# XMOS_TSBOARD_Xmos.net
KiCad netlist of a schematic drawn in Altium Designer
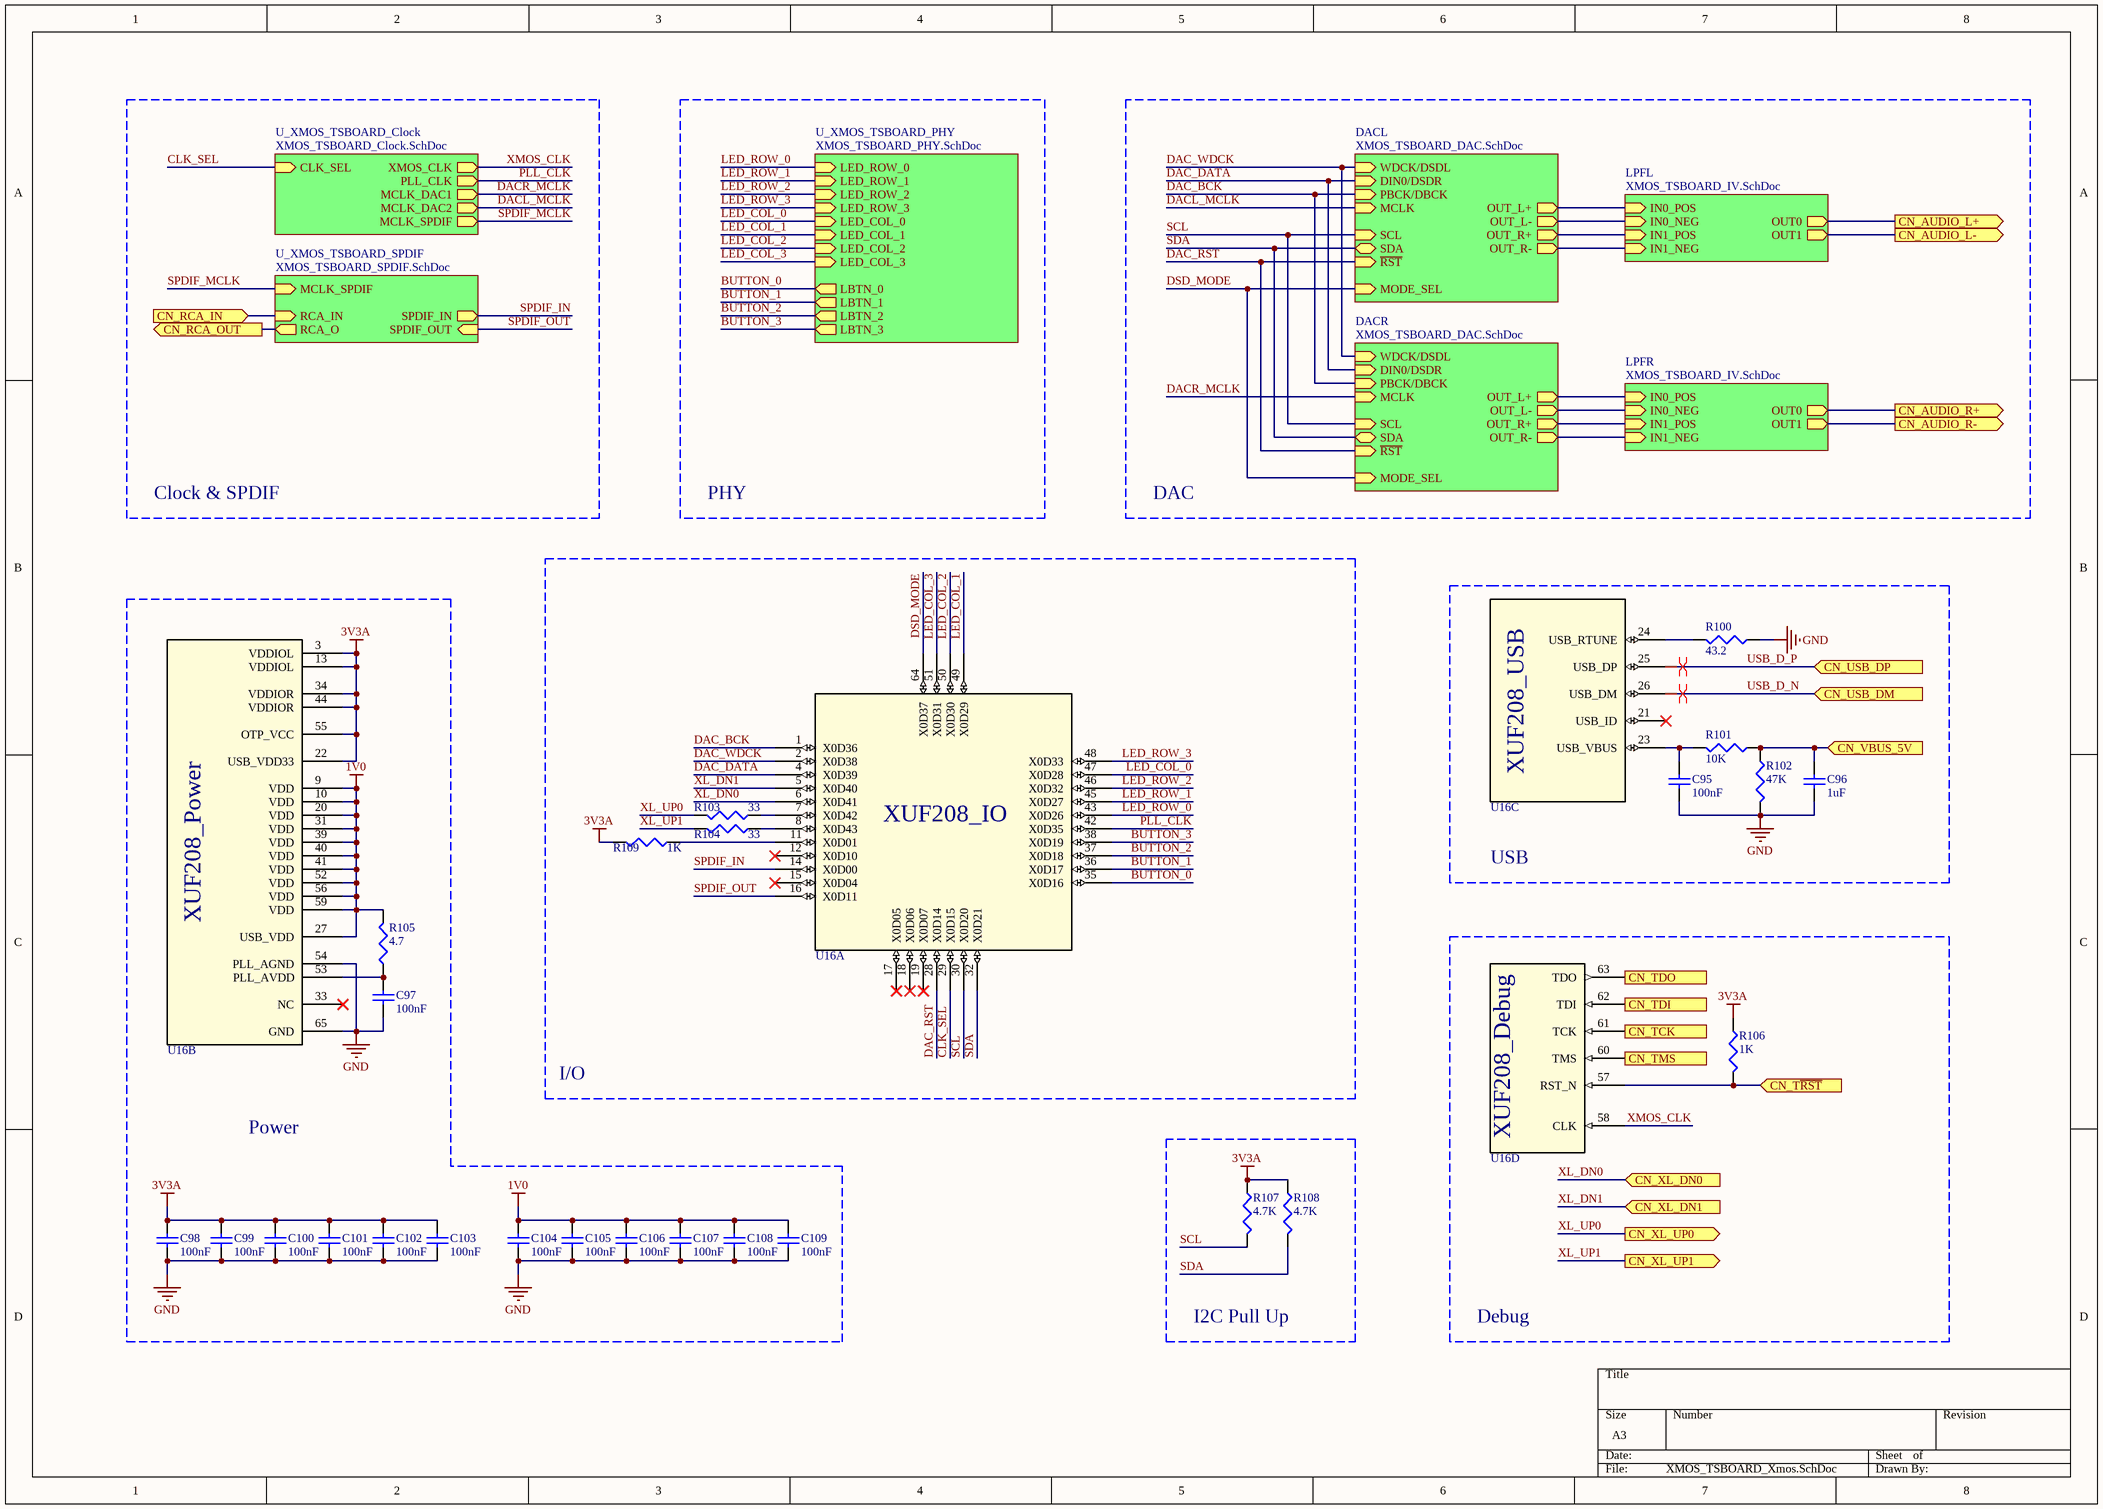
[diagram p0: XMOS_TSBOARD_Xmos.SchDoc]

(export (version "E")
  (design (tool "Eeschema 10.0.6"))
  (components
    (comp (ref "C95")
      (value "100nF")
      (footprint "1608[0603]")
      (description "Capacitor (Semiconductor SIM Model)")
      (fields (field (name "Comment") "Cap Semi") (field (name "PUBLISHER") "Altium Limited"))
      (libsource (lib "Miscellaneous Devices") (part "Cap Semi"))
    )
    (comp (ref "C96")
      (value "1uF")
      (footprint "1608[0603]")
      (description "Capacitor (Semiconductor SIM Model)")
      (fields (field (name "Comment") "Cap Semi") (field (name "PUBLISHER") "Altium Limited"))
      (libsource (lib "Miscellaneous Devices") (part "Cap Semi"))
    )
    (comp (ref "C97")
      (value "100nF")
      (footprint "1608[0603]")
      (description "Capacitor (Semiconductor SIM Model)")
      (fields (field (name "Comment") "Cap Semi") (field (name "PUBLISHER") "Altium Limited"))
      (libsource (lib "Miscellaneous Devices") (part "Cap Semi"))
    )
    (comp (ref "C98")
      (value "100nF")
      (footprint "1608[0603]")
      (description "Capacitor (Semiconductor SIM Model)")
      (fields (field (name "Comment") "Cap Semi") (field (name "PUBLISHER") "Altium Limited"))
      (libsource (lib "Miscellaneous Devices") (part "Cap Semi"))
    )
    (comp (ref "C99")
      (value "100nF")
      (footprint "1608[0603]")
      (description "Capacitor (Semiconductor SIM Model)")
      (fields (field (name "Comment") "Cap Semi") (field (name "PUBLISHER") "Altium Limited"))
      (libsource (lib "Miscellaneous Devices") (part "Cap Semi"))
    )
    (comp (ref "C100")
      (value "100nF")
      (footprint "1608[0603]")
      (description "Capacitor (Semiconductor SIM Model)")
      (fields (field (name "Comment") "Cap Semi") (field (name "PUBLISHER") "Altium Limited"))
      (libsource (lib "Miscellaneous Devices") (part "Cap Semi"))
    )
    (comp (ref "C101")
      (value "100nF")
      (footprint "1608[0603]")
      (description "Capacitor (Semiconductor SIM Model)")
      (fields (field (name "Comment") "Cap Semi") (field (name "PUBLISHER") "Altium Limited"))
      (libsource (lib "Miscellaneous Devices") (part "Cap Semi"))
    )
    (comp (ref "C102")
      (value "100nF")
      (footprint "1608[0603]")
      (description "Capacitor (Semiconductor SIM Model)")
      (fields (field (name "Comment") "Cap Semi") (field (name "PUBLISHER") "Altium Limited"))
      (libsource (lib "Miscellaneous Devices") (part "Cap Semi"))
    )
    (comp (ref "C103")
      (value "100nF")
      (footprint "1608[0603]")
      (description "Capacitor (Semiconductor SIM Model)")
      (fields (field (name "Comment") "Cap Semi") (field (name "PUBLISHER") "Altium Limited"))
      (libsource (lib "Miscellaneous Devices") (part "Cap Semi"))
    )
    (comp (ref "C104")
      (value "100nF")
      (footprint "1608[0603]")
      (description "Capacitor (Semiconductor SIM Model)")
      (fields (field (name "Comment") "Cap Semi") (field (name "PUBLISHER") "Altium Limited"))
      (libsource (lib "Miscellaneous Devices") (part "Cap Semi"))
    )
    (comp (ref "C105")
      (value "100nF")
      (footprint "1608[0603]")
      (description "Capacitor (Semiconductor SIM Model)")
      (fields (field (name "Comment") "Cap Semi") (field (name "PUBLISHER") "Altium Limited"))
      (libsource (lib "Miscellaneous Devices") (part "Cap Semi"))
    )
    (comp (ref "C106")
      (value "100nF")
      (footprint "1608[0603]")
      (description "Capacitor (Semiconductor SIM Model)")
      (fields (field (name "Comment") "Cap Semi") (field (name "PUBLISHER") "Altium Limited"))
      (libsource (lib "Miscellaneous Devices") (part "Cap Semi"))
    )
    (comp (ref "C107")
      (value "100nF")
      (footprint "1608[0603]")
      (description "Capacitor (Semiconductor SIM Model)")
      (fields (field (name "Comment") "Cap Semi") (field (name "PUBLISHER") "Altium Limited"))
      (libsource (lib "Miscellaneous Devices") (part "Cap Semi"))
    )
    (comp (ref "C108")
      (value "100nF")
      (footprint "1608[0603]")
      (description "Capacitor (Semiconductor SIM Model)")
      (fields (field (name "Comment") "Cap Semi") (field (name "PUBLISHER") "Altium Limited"))
      (libsource (lib "Miscellaneous Devices") (part "Cap Semi"))
    )
    (comp (ref "C109")
      (value "100nF")
      (footprint "1608[0603]")
      (description "Capacitor (Semiconductor SIM Model)")
      (fields (field (name "Comment") "Cap Semi") (field (name "PUBLISHER") "Altium Limited"))
      (libsource (lib "Miscellaneous Devices") (part "Cap Semi"))
    )
    (comp (ref "R100")
      (value "43.2")
      (footprint "J1-0603")
      (description "Resistor")
      (fields (field (name "Comment") "Res3") (field (name "PUBLISHER") "Altium Limited"))
      (libsource (lib "Miscellaneous Devices") (part "Res3"))
    )
    (comp (ref "R101")
      (value "10K")
      (footprint "J1-0603")
      (description "Resistor")
      (fields (field (name "Comment") "Res3") (field (name "PUBLISHER") "Altium Limited"))
      (libsource (lib "Miscellaneous Devices") (part "Res3"))
    )
    (comp (ref "R102")
      (value "47K")
      (footprint "J1-0603")
      (description "Resistor")
      (fields (field (name "Comment") "Res3") (field (name "PUBLISHER") "Altium Limited"))
      (libsource (lib "Miscellaneous Devices") (part "Res3"))
    )
    (comp (ref "R103")
      (value "33")
      (footprint "J1-0603")
      (description "Resistor")
      (fields (field (name "Comment") "Res3") (field (name "PUBLISHER") "Altium Limited"))
      (libsource (lib "Miscellaneous Devices") (part "Res3"))
    )
    (comp (ref "R104")
      (value "33")
      (footprint "J1-0603")
      (description "Resistor")
      (fields (field (name "Comment") "Res3") (field (name "PUBLISHER") "Altium Limited"))
      (libsource (lib "Miscellaneous Devices") (part "Res3"))
    )
    (comp (ref "R105")
      (value "4.7")
      (footprint "J1-0603")
      (description "Resistor")
      (fields (field (name "Comment") "Res3") (field (name "PUBLISHER") "Altium Limited"))
      (libsource (lib "Miscellaneous Devices") (part "Res3"))
    )
    (comp (ref "R106")
      (value "1K")
      (footprint "J1-0603")
      (description "Resistor")
      (fields (field (name "Comment") "Res3") (field (name "PUBLISHER") "Altium Limited"))
      (libsource (lib "Miscellaneous Devices") (part "Res3"))
    )
    (comp (ref "R107")
      (value "4.7K")
      (footprint "J1-0603")
      (description "Resistor")
      (fields (field (name "Comment") "Res3") (field (name "PUBLISHER") "Altium Limited"))
      (libsource (lib "Miscellaneous Devices") (part "Res3"))
    )
    (comp (ref "R108")
      (value "4.7K")
      (footprint "J1-0603")
      (description "Resistor")
      (fields (field (name "Comment") "Res3") (field (name "PUBLISHER") "Altium Limited"))
      (libsource (lib "Miscellaneous Devices") (part "Res3"))
    )
    (comp (ref "R109")
      (value "1K")
      (footprint "J1-0603")
      (description "Resistor")
      (fields (field (name "Comment") "Res3") (field (name "PUBLISHER") "Altium Limited"))
      (libsource (lib "Miscellaneous Devices") (part "Res3"))
    )
    (comp (ref "U16")
      (value "XUF208-256-TQ64")
      (footprint "TQFP64")
      (description "xCORE Multicore Microcontrollers")
      (libsource (lib "Troposphere_lib") (part "XUF208-256-TQ64"))
    )
  )
  (nets
    (net (code "1") (name "/BUTTON_0") (class "Default")
      (node (ref "U16") (pin "35") (pinfunction "X0D16_35") (pintype "bidirectional"))
    )
    (net (code "2") (name "/BUTTON_1") (class "Default")
      (node (ref "U16") (pin "36") (pinfunction "X0D17_36") (pintype "bidirectional"))
    )
    (net (code "3") (name "/BUTTON_2") (class "Default")
      (node (ref "U16") (pin "37") (pinfunction "X0D18_37") (pintype "bidirectional"))
    )
    (net (code "4") (name "/BUTTON_3") (class "Default")
      (node (ref "U16") (pin "38") (pinfunction "X0D19_38") (pintype "bidirectional"))
    )
    (net (code "5") (name "/CLK_SEL") (class "Default")
      (node (ref "U16") (pin "29") (pinfunction "X0D15_29") (pintype "bidirectional"))
    )
    (net (code "12") (name "/CN_TCK") (class "Default")
      (node (ref "U16") (pin "61") (pinfunction "TCK_61") (pintype "input"))
    )
    (net (code "13") (name "/CN_TDI") (class "Default")
      (node (ref "U16") (pin "62") (pinfunction "TDI_62") (pintype "input"))
    )
    (net (code "14") (name "/CN_TDO") (class "Default")
      (node (ref "U16") (pin "63") (pinfunction "TDO_63") (pintype "output"))
    )
    (net (code "15") (name "/CN_TMS") (class "Default")
      (node (ref "U16") (pin "60") (pinfunction "TMS_60") (pintype "input"))
    )
    (net (code "16") (name "/CN_T~{RST}") (class "Default")
      (node (ref "R106") (pin "2") (pinfunction "2_2") (pintype "passive"))
      (node (ref "U16") (pin "57") (pinfunction "RST_N_57") (pintype "input"))
    )
    (net (code "17") (name "/CN_VBUS_5V") (class "Default")
      (node (ref "C96") (pin "2") (pinfunction "2_2") (pintype "passive"))
      (node (ref "R101") (pin "1") (pinfunction "1_1") (pintype "passive"))
      (node (ref "R102") (pin "1") (pinfunction "1_1") (pintype "passive"))
    )
    (net (code "20") (name "/DAC_BCK") (class "Default")
      (node (ref "U16") (pin "1") (pinfunction "X0D36_1") (pintype "bidirectional"))
    )
    (net (code "21") (name "/DAC_DATA") (class "Default")
      (node (ref "U16") (pin "4") (pinfunction "X0D39_4") (pintype "bidirectional"))
    )
    (net (code "22") (name "/DAC_RST") (class "Default")
      (node (ref "U16") (pin "28") (pinfunction "X0D14_28") (pintype "bidirectional"))
    )
    (net (code "23") (name "/DAC_WDCK") (class "Default")
      (node (ref "U16") (pin "2") (pinfunction "X0D38_2") (pintype "bidirectional"))
    )
    (net (code "24") (name "/DSD_MODE") (class "Default")
      (node (ref "U16") (pin "64") (pinfunction "X0D37_64") (pintype "bidirectional"))
    )
    (net (code "25") (name "/LED_COL_0") (class "Default")
      (node (ref "U16") (pin "47") (pinfunction "X0D28_47") (pintype "bidirectional"))
    )
    (net (code "26") (name "/LED_COL_1") (class "Default")
      (node (ref "U16") (pin "49") (pinfunction "X0D29_49") (pintype "bidirectional"))
    )
    (net (code "27") (name "/LED_COL_2") (class "Default")
      (node (ref "U16") (pin "50") (pinfunction "X0D30_50") (pintype "bidirectional"))
    )
    (net (code "28") (name "/LED_COL_3") (class "Default")
      (node (ref "U16") (pin "51") (pinfunction "X0D31_51") (pintype "bidirectional"))
    )
    (net (code "29") (name "/LED_ROW_0") (class "Default")
      (node (ref "U16") (pin "43") (pinfunction "X0D26_43") (pintype "bidirectional"))
    )
    (net (code "30") (name "/LED_ROW_1") (class "Default")
      (node (ref "U16") (pin "45") (pinfunction "X0D27_45") (pintype "bidirectional"))
    )
    (net (code "31") (name "/LED_ROW_2") (class "Default")
      (node (ref "U16") (pin "46") (pinfunction "X0D32_46") (pintype "bidirectional"))
    )
    (net (code "32") (name "/LED_ROW_3") (class "Default")
      (node (ref "U16") (pin "48") (pinfunction "X0D33_48") (pintype "bidirectional"))
    )
    (net (code "41") (name "/PLL_CLK") (class "Default")
      (node (ref "U16") (pin "42") (pinfunction "X0D35_42") (pintype "bidirectional"))
    )
    (net (code "42") (name "/SCL") (class "Default")
      (node (ref "R107") (pin "2") (pinfunction "2_2") (pintype "passive"))
      (node (ref "U16") (pin "30") (pinfunction "X0D20_30") (pintype "bidirectional"))
    )
    (net (code "43") (name "/SDA") (class "Default")
      (node (ref "R108") (pin "2") (pinfunction "2_2") (pintype "passive"))
      (node (ref "U16") (pin "32") (pinfunction "X0D21_32") (pintype "bidirectional"))
    )
    (net (code "44") (name "/SPDIF_IN") (class "Default")
      (node (ref "U16") (pin "14") (pinfunction "X0D00_14") (pintype "bidirectional"))
    )
    (net (code "46") (name "/SPDIF_OUT") (class "Default")
      (node (ref "U16") (pin "16") (pinfunction "X0D11_16") (pintype "bidirectional"))
    )
    (net (code "47") (name "/USB_D_N") (class "Default")
      (node (ref "U16") (pin "26") (pinfunction "USB_DM_26") (pintype "bidirectional"))
    )
    (net (code "48") (name "/USB_D_P") (class "Default")
      (node (ref "U16") (pin "25") (pinfunction "USB_DP_25") (pintype "bidirectional"))
    )
    (net (code "49") (name "/XL_DN0") (class "Default")
      (node (ref "U16") (pin "6") (pinfunction "X0D41_6") (pintype "bidirectional"))
    )
    (net (code "50") (name "/XL_DN1") (class "Default")
      (node (ref "U16") (pin "5") (pinfunction "X0D40_5") (pintype "bidirectional"))
    )
    (net (code "51") (name "/XL_UP0") (class "Default")
      (node (ref "R103") (pin "2") (pinfunction "2_2") (pintype "passive"))
    )
    (net (code "52") (name "/XL_UP1") (class "Default")
      (node (ref "R104") (pin "2") (pinfunction "2_2") (pintype "passive"))
    )
    (net (code "53") (name "/XMOS_CLK") (class "Default")
      (node (ref "U16") (pin "58") (pinfunction "CLK_58") (pintype "input"))
    )
    (net (code "54") (name "1V0") (class "Default")
      (node (ref "C104") (pin "2") (pinfunction "2_2") (pintype "passive"))
      (node (ref "C105") (pin "2") (pinfunction "2_2") (pintype "passive"))
      (node (ref "C106") (pin "2") (pinfunction "2_2") (pintype "passive"))
      (node (ref "C107") (pin "2") (pinfunction "2_2") (pintype "passive"))
      (node (ref "C108") (pin "2") (pinfunction "2_2") (pintype "passive"))
      (node (ref "C109") (pin "2") (pinfunction "2_2") (pintype "passive"))
      (node (ref "R105") (pin "2") (pinfunction "2_2") (pintype "passive"))
      (node (ref "U16") (pin "10") (pinfunction "VDD_10") (pintype "power_in"))
      (node (ref "U16") (pin "20") (pinfunction "VDD_20") (pintype "power_in"))
      (node (ref "U16") (pin "27") (pinfunction "USB_VDD_27") (pintype "power_in"))
      (node (ref "U16") (pin "31") (pinfunction "VDD_31") (pintype "power_in"))
      (node (ref "U16") (pin "39") (pinfunction "VDD_39") (pintype "power_in"))
      (node (ref "U16") (pin "40") (pinfunction "VDD_40") (pintype "power_in"))
      (node (ref "U16") (pin "41") (pinfunction "VDD_41") (pintype "power_in"))
      (node (ref "U16") (pin "52") (pinfunction "VDD_52") (pintype "power_in"))
      (node (ref "U16") (pin "56") (pinfunction "VDD_56") (pintype "power_in"))
      (node (ref "U16") (pin "59") (pinfunction "VDD_59") (pintype "power_in"))
      (node (ref "U16") (pin "9") (pinfunction "VDD_9") (pintype "power_in"))
    )
    (net (code "55") (name "3V3A") (class "Default")
      (node (ref "C100") (pin "2") (pinfunction "2_2") (pintype "passive"))
      (node (ref "C101") (pin "2") (pinfunction "2_2") (pintype "passive"))
      (node (ref "C102") (pin "2") (pinfunction "2_2") (pintype "passive"))
      (node (ref "C103") (pin "2") (pinfunction "2_2") (pintype "passive"))
      (node (ref "C98") (pin "2") (pinfunction "2_2") (pintype "passive"))
      (node (ref "C99") (pin "2") (pinfunction "2_2") (pintype "passive"))
      (node (ref "R106") (pin "1") (pinfunction "1_1") (pintype "passive"))
      (node (ref "R107") (pin "1") (pinfunction "1_1") (pintype "passive"))
      (node (ref "R108") (pin "1") (pinfunction "1_1") (pintype "passive"))
      (node (ref "R109") (pin "2") (pinfunction "2_2") (pintype "passive"))
      (node (ref "U16") (pin "13") (pinfunction "VDDIOL_13") (pintype "power_in"))
      (node (ref "U16") (pin "22") (pinfunction "USB_VDD33_22") (pintype "power_in"))
      (node (ref "U16") (pin "3") (pinfunction "VDDIOL_3") (pintype "power_in"))
      (node (ref "U16") (pin "34") (pinfunction "VDDIOR_34") (pintype "power_in"))
      (node (ref "U16") (pin "44") (pinfunction "VDDIOR_44") (pintype "power_in"))
      (node (ref "U16") (pin "55") (pinfunction "OTP_VCC_55") (pintype "power_in"))
    )
    (net (code "56") (name "GND") (class "Default")
      (node (ref "C100") (pin "1") (pinfunction "1_1") (pintype "passive"))
      (node (ref "C101") (pin "1") (pinfunction "1_1") (pintype "passive"))
      (node (ref "C102") (pin "1") (pinfunction "1_1") (pintype "passive"))
      (node (ref "C103") (pin "1") (pinfunction "1_1") (pintype "passive"))
      (node (ref "C104") (pin "1") (pinfunction "1_1") (pintype "passive"))
      (node (ref "C105") (pin "1") (pinfunction "1_1") (pintype "passive"))
      (node (ref "C106") (pin "1") (pinfunction "1_1") (pintype "passive"))
      (node (ref "C107") (pin "1") (pinfunction "1_1") (pintype "passive"))
      (node (ref "C108") (pin "1") (pinfunction "1_1") (pintype "passive"))
      (node (ref "C109") (pin "1") (pinfunction "1_1") (pintype "passive"))
      (node (ref "C95") (pin "1") (pinfunction "1_1") (pintype "passive"))
      (node (ref "C96") (pin "1") (pinfunction "1_1") (pintype "passive"))
      (node (ref "C97") (pin "1") (pinfunction "1_1") (pintype "passive"))
      (node (ref "C98") (pin "1") (pinfunction "1_1") (pintype "passive"))
      (node (ref "C99") (pin "1") (pinfunction "1_1") (pintype "passive"))
      (node (ref "R100") (pin "1") (pinfunction "1_1") (pintype "passive"))
      (node (ref "R102") (pin "2") (pinfunction "2_2") (pintype "passive"))
      (node (ref "U16") (pin "54") (pinfunction "PLL_AGND_54") (pintype "power_in"))
      (node (ref "U16") (pin "65") (pinfunction "GND_65") (pintype "power_in"))
    )
    (net (code "57") (name "Net-(U16A-X0D01)") (class "Default")
      (node (ref "R109") (pin "1") (pinfunction "1_1") (pintype "passive"))
      (node (ref "U16") (pin "11") (pinfunction "X0D01_11") (pintype "bidirectional"))
    )
    (net (code "58") (name "Net-(U16A-X0D42)") (class "Default")
      (node (ref "R103") (pin "1") (pinfunction "1_1") (pintype "passive"))
      (node (ref "U16") (pin "7") (pinfunction "X0D42_7") (pintype "bidirectional"))
    )
    (net (code "59") (name "Net-(U16A-X0D43)") (class "Default")
      (node (ref "R104") (pin "1") (pinfunction "1_1") (pintype "passive"))
      (node (ref "U16") (pin "8") (pinfunction "X0D43_8") (pintype "bidirectional"))
    )
    (net (code "60") (name "Net-(U16B-PLL_AVDD)") (class "Default")
      (node (ref "C97") (pin "2") (pinfunction "2_2") (pintype "passive"))
      (node (ref "R105") (pin "1") (pinfunction "1_1") (pintype "passive"))
      (node (ref "U16") (pin "53") (pinfunction "PLL_AVDD_53") (pintype "power_in"))
    )
    (net (code "61") (name "Net-(U16C-USB_RTUNE)") (class "Default")
      (node (ref "R100") (pin "2") (pinfunction "2_2") (pintype "passive"))
      (node (ref "U16") (pin "24") (pinfunction "USB_RTUNE_24") (pintype "bidirectional"))
    )
    (net (code "62") (name "Net-(U16C-USB_VBUS)") (class "Default")
      (node (ref "C95") (pin "2") (pinfunction "2_2") (pintype "passive"))
      (node (ref "R101") (pin "2") (pinfunction "2_2") (pintype "passive"))
      (node (ref "U16") (pin "23") (pinfunction "USB_VBUS_23") (pintype "bidirectional"))
    )
    (net (code "63") (name "unconnected-(U16A-X0D04-Pad15)") (class "Default")
      (node (ref "U16") (pin "15") (pinfunction "X0D04_15") (pintype "bidirectional+no_connect"))
    )
    (net (code "64") (name "unconnected-(U16A-X0D05-Pad17)") (class "Default")
      (node (ref "U16") (pin "17") (pinfunction "X0D05_17") (pintype "bidirectional+no_connect"))
    )
    (net (code "65") (name "unconnected-(U16A-X0D06-Pad18)") (class "Default")
      (node (ref "U16") (pin "18") (pinfunction "X0D06_18") (pintype "bidirectional+no_connect"))
    )
    (net (code "66") (name "unconnected-(U16A-X0D07-Pad19)") (class "Default")
      (node (ref "U16") (pin "19") (pinfunction "X0D07_19") (pintype "bidirectional+no_connect"))
    )
    (net (code "67") (name "unconnected-(U16A-X0D10-Pad12)") (class "Default")
      (node (ref "U16") (pin "12") (pinfunction "X0D10_12") (pintype "bidirectional+no_connect"))
    )
    (net (code "68") (name "unconnected-(U16B-NC-Pad33)") (class "Default")
      (node (ref "U16") (pin "33") (pinfunction "NC_33") (pintype "passive+no_connect"))
    )
    (net (code "69") (name "unconnected-(U16C-USB_ID-Pad21)") (class "Default")
      (node (ref "U16") (pin "21") (pinfunction "USB_ID_21") (pintype "bidirectional+no_connect"))
    )
  )
)
